# tr2_redraw.net
KiCad netlist of a schematic drawn in EAGLE
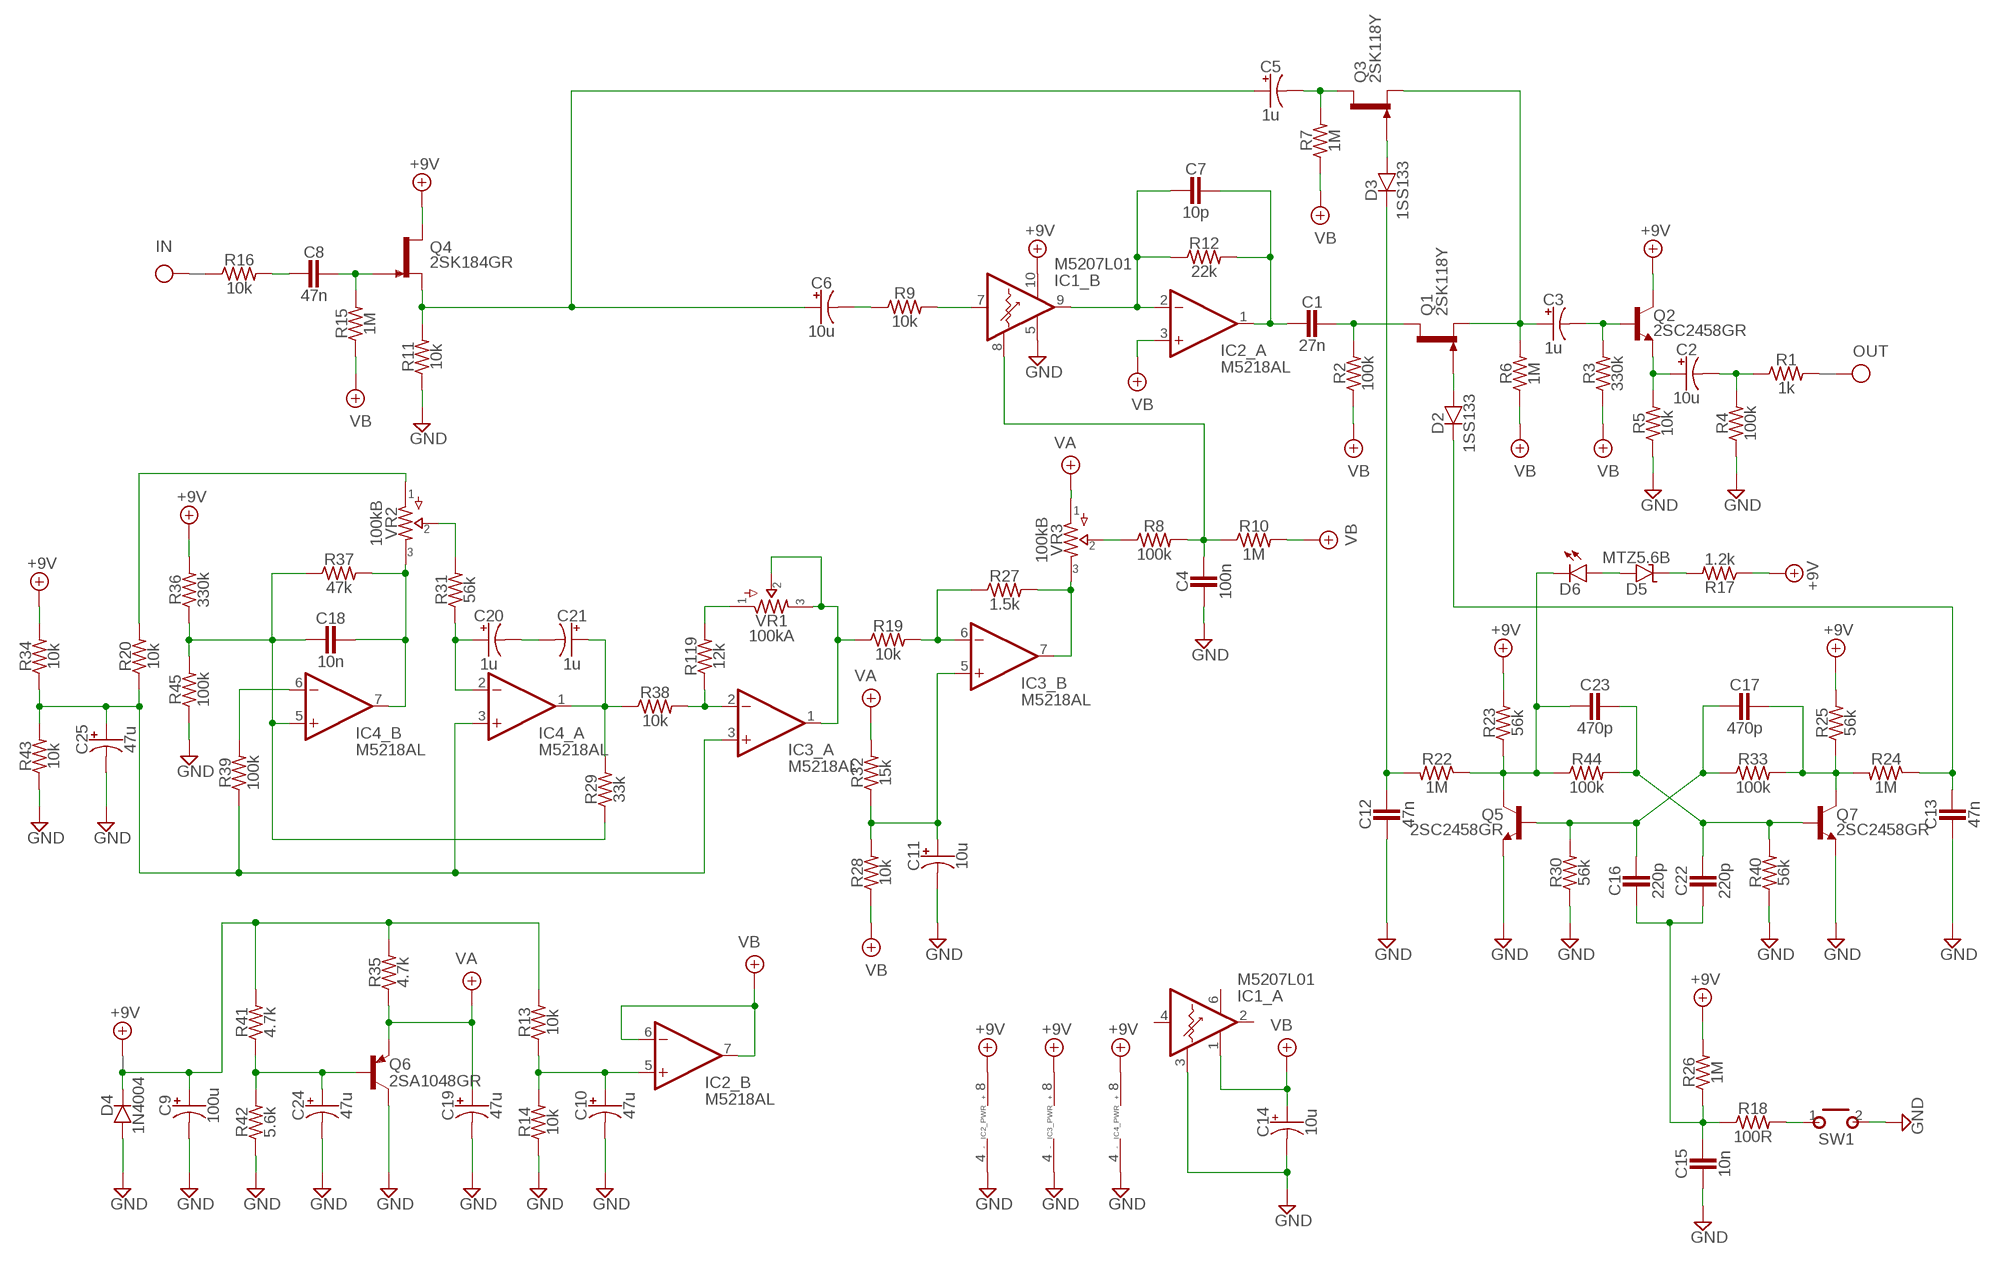
[diagram p0: schematic, sheet 1]

(export (version "E")
  (design (tool "Eeschema 10.0.6"))
  (components
    (comp (ref "C1")
      (value "27n")
      (footprint "eagle-import:BOX_SMALL")
      (libsource (lib "eagle-import") (part "CER/FILMBOX.1"))
    )
    (comp (ref "C2")
      (value "10u")
      (footprint "eagle-import:040_020")
      (libsource (lib "eagle-import") (part "0400"))
    )
    (comp (ref "C3")
      (value "1u")
      (footprint "eagle-import:040_020")
      (libsource (lib "eagle-import") (part "0400"))
    )
    (comp (ref "C4")
      (value "100n")
      (footprint "eagle-import:BOX_SMALL")
      (libsource (lib "eagle-import") (part "CER/FILMBOX.1"))
    )
    (comp (ref "C5")
      (value "1u")
      (footprint "eagle-import:040_020")
      (libsource (lib "eagle-import") (part "0400"))
    )
    (comp (ref "C6")
      (value "10u")
      (footprint "eagle-import:040_020")
      (libsource (lib "eagle-import") (part "0400"))
    )
    (comp (ref "C7")
      (value "10p")
      (footprint "eagle-import:BOX_SMALL")
      (libsource (lib "eagle-import") (part "CER/FILMBOX.1"))
    )
    (comp (ref "C8")
      (value "47n")
      (footprint "eagle-import:BOX_SMALL")
      (libsource (lib "eagle-import") (part "CER/FILMBOX.1"))
    )
    (comp (ref "C9")
      (value "100u")
      (footprint "eagle-import:040_020")
      (libsource (lib "eagle-import") (part "0400"))
    )
    (comp (ref "C10")
      (value "47u")
      (footprint "eagle-import:040_020")
      (libsource (lib "eagle-import") (part "0400"))
    )
    (comp (ref "C11")
      (value "10u")
      (footprint "eagle-import:040_020")
      (libsource (lib "eagle-import") (part "0400"))
    )
    (comp (ref "C12")
      (value "47n")
      (footprint "eagle-import:BOX_SMALL")
      (libsource (lib "eagle-import") (part "CER/FILMBOX.1"))
    )
    (comp (ref "C13")
      (value "47n")
      (footprint "eagle-import:BOX_SMALL")
      (libsource (lib "eagle-import") (part "CER/FILMBOX.1"))
    )
    (comp (ref "C14")
      (value "10u")
      (footprint "eagle-import:040_020")
      (libsource (lib "eagle-import") (part "0400"))
    )
    (comp (ref "C15")
      (value "10n")
      (footprint "eagle-import:BOX_SMALL")
      (libsource (lib "eagle-import") (part "CER/FILMBOX.1"))
    )
    (comp (ref "C16")
      (value "220p")
      (footprint "eagle-import:BOX_SMALL")
      (libsource (lib "eagle-import") (part "CER/FILMBOX.1"))
    )
    (comp (ref "C17")
      (value "470p")
      (footprint "eagle-import:BOX_SMALL")
      (libsource (lib "eagle-import") (part "CER/FILMBOX.1"))
    )
    (comp (ref "C18")
      (value "10n")
      (footprint "eagle-import:BOX_SMALL")
      (libsource (lib "eagle-import") (part "CER/FILMBOX.1"))
    )
    (comp (ref "C19")
      (value "47u")
      (footprint "eagle-import:040_020")
      (libsource (lib "eagle-import") (part "0400"))
    )
    (comp (ref "C20")
      (value "1u")
      (footprint "eagle-import:040_020")
      (libsource (lib "eagle-import") (part "0400"))
    )
    (comp (ref "C21")
      (value "1u")
      (footprint "eagle-import:040_020")
      (libsource (lib "eagle-import") (part "0400"))
    )
    (comp (ref "C22")
      (value "220p")
      (footprint "eagle-import:BOX_SMALL")
      (libsource (lib "eagle-import") (part "CER/FILMBOX.1"))
    )
    (comp (ref "C23")
      (value "470p")
      (footprint "eagle-import:BOX_SMALL")
      (libsource (lib "eagle-import") (part "CER/FILMBOX.1"))
    )
    (comp (ref "C24")
      (value "47u")
      (footprint "eagle-import:040_020")
      (libsource (lib "eagle-import") (part "0400"))
    )
    (comp (ref "C25")
      (value "47u")
      (footprint "eagle-import:040_020")
      (libsource (lib "eagle-import") (part "0400"))
    )
    (comp (ref "D2")
      (value "1SS133")
      (footprint "eagle-import:DO35-2")
      (libsource (lib "eagle-import") (part "DO35.2"))
    )
    (comp (ref "D3")
      (value "1SS133")
      (footprint "eagle-import:DO35-2")
      (libsource (lib "eagle-import") (part "DO35.2"))
    )
    (comp (ref "D4")
      (value "1N4004")
      (footprint "eagle-import:DO35-2")
      (libsource (lib "eagle-import") (part "DO35.2"))
    )
    (comp (ref "D5")
      (value "MTZ5.6B")
      (footprint "eagle-import:DO41-2")
      (libsource (lib "eagle-import") (part "ZENER.2"))
    )
    (comp (ref "D6")
      (value "LN-28RP")
      (footprint "eagle-import:3MM_D")
      (libsource (lib "eagle-import") (part "LED"))
    )
    (comp (ref "IC1")
      (value "M5207L01")
      (footprint "eagle-import:SIL10")
      (libsource (lib "eagle-import") (part "M5207L01"))
    )
    (comp (ref "IC2")
      (value "M5218AL")
      (footprint "eagle-import:DIL0")
      (libsource (lib "eagle-import") (part "DUALTH"))
    )
    (comp (ref "IC3")
      (value "M5218AL")
      (footprint "eagle-import:DIL0")
      (libsource (lib "eagle-import") (part "DUALTH"))
    )
    (comp (ref "IC4")
      (value "M5218AL")
      (footprint "eagle-import:DIL0")
      (libsource (lib "eagle-import") (part "DUALTH"))
    )
    (comp (ref "Q1")
      (value "2SK118Y")
      (footprint "eagle-import:TO92-")
      (libsource (lib "eagle-import") (part "2N3819TO-92S"))
    )
    (comp (ref "Q2")
      (value "2SC2458GR")
      (footprint "eagle-import:TO92-")
      (libsource (lib "eagle-import") (part "2SC828A"))
    )
    (comp (ref "Q3")
      (value "2SK118Y")
      (footprint "eagle-import:TO92-")
      (libsource (lib "eagle-import") (part "2N3819TO-92S"))
    )
    (comp (ref "Q4")
      (value "2SK184GR")
      (footprint "eagle-import:TO92-")
      (libsource (lib "eagle-import") (part "2N3819TO-92S"))
    )
    (comp (ref "Q5")
      (value "2SC2458GR")
      (footprint "eagle-import:TO92-")
      (libsource (lib "eagle-import") (part "2SC828A"))
    )
    (comp (ref "Q6")
      (value "2SA1048GR")
      (footprint "eagle-import:TO92-")
      (libsource (lib "eagle-import") (part "2N3906-"))
    )
    (comp (ref "Q7")
      (value "2SC2458GR")
      (footprint "eagle-import:TO92-")
      (libsource (lib "eagle-import") (part "2SC828A"))
    )
    (comp (ref "R1")
      (value "1k")
      (footprint "eagle-import:R0207_3")
      (libsource (lib "eagle-import") (part "R_.3B"))
    )
    (comp (ref "R2")
      (value "100k")
      (footprint "eagle-import:R0207_3")
      (libsource (lib "eagle-import") (part "R_.3B"))
    )
    (comp (ref "R3")
      (value "330k")
      (footprint "eagle-import:R0207_3")
      (libsource (lib "eagle-import") (part "R_.3B"))
    )
    (comp (ref "R4")
      (value "100k")
      (footprint "eagle-import:R0207_3")
      (libsource (lib "eagle-import") (part "R_.3B"))
    )
    (comp (ref "R5")
      (value "10k")
      (footprint "eagle-import:R0207_3")
      (libsource (lib "eagle-import") (part "R_.3B"))
    )
    (comp (ref "R6")
      (value "1M")
      (footprint "eagle-import:R0207_3")
      (libsource (lib "eagle-import") (part "R_.3B"))
    )
    (comp (ref "R7")
      (value "1M")
      (footprint "eagle-import:R0207_3")
      (libsource (lib "eagle-import") (part "R_.3B"))
    )
    (comp (ref "R8")
      (value "100k")
      (footprint "eagle-import:R0207_3")
      (libsource (lib "eagle-import") (part "R_.3B"))
    )
    (comp (ref "R9")
      (value "10k")
      (footprint "eagle-import:R0207_3")
      (libsource (lib "eagle-import") (part "R_.3B"))
    )
    (comp (ref "R10")
      (value "1M")
      (footprint "eagle-import:R0207_3")
      (libsource (lib "eagle-import") (part "R_.3B"))
    )
    (comp (ref "R11")
      (value "10k")
      (footprint "eagle-import:R0207_3")
      (libsource (lib "eagle-import") (part "R_.3B"))
    )
    (comp (ref "R12")
      (value "22k")
      (footprint "eagle-import:R0207_3")
      (libsource (lib "eagle-import") (part "R_.3B"))
    )
    (comp (ref "R13")
      (value "10k")
      (footprint "eagle-import:R0207_3")
      (libsource (lib "eagle-import") (part "R_.3B"))
    )
    (comp (ref "R14")
      (value "10k")
      (footprint "eagle-import:R0207_3")
      (libsource (lib "eagle-import") (part "R_.3B"))
    )
    (comp (ref "R15")
      (value "1M")
      (footprint "eagle-import:R0207_3")
      (libsource (lib "eagle-import") (part "R_.3B"))
    )
    (comp (ref "R16")
      (value "10k")
      (footprint "eagle-import:R0207_3")
      (libsource (lib "eagle-import") (part "R_.3B"))
    )
    (comp (ref "R17")
      (value "1.2k")
      (footprint "eagle-import:R0207_3")
      (libsource (lib "eagle-import") (part "R_.3B"))
    )
    (comp (ref "R18")
      (value "100R")
      (footprint "eagle-import:R0207_3")
      (libsource (lib "eagle-import") (part "R_.3B"))
    )
    (comp (ref "R19")
      (value "10k")
      (footprint "eagle-import:R0207_3")
      (libsource (lib "eagle-import") (part "R_.3B"))
    )
    (comp (ref "R20")
      (value "10k")
      (footprint "eagle-import:R0207_3")
      (libsource (lib "eagle-import") (part "R_.3B"))
    )
    (comp (ref "R22")
      (value "1M")
      (footprint "eagle-import:R0207_3")
      (libsource (lib "eagle-import") (part "R_.3B"))
    )
    (comp (ref "R23")
      (value "56k")
      (footprint "eagle-import:R0207_3")
      (libsource (lib "eagle-import") (part "R_.3B"))
    )
    (comp (ref "R24")
      (value "1M")
      (footprint "eagle-import:R0207_3")
      (libsource (lib "eagle-import") (part "R_.3B"))
    )
    (comp (ref "R25")
      (value "56k")
      (footprint "eagle-import:R0207_3")
      (libsource (lib "eagle-import") (part "R_.3B"))
    )
    (comp (ref "R26")
      (value "1M")
      (footprint "eagle-import:R0207_3")
      (libsource (lib "eagle-import") (part "R_.3B"))
    )
    (comp (ref "R27")
      (value "1.5k")
      (footprint "eagle-import:R0207_3")
      (libsource (lib "eagle-import") (part "R_.3B"))
    )
    (comp (ref "R28")
      (value "10k")
      (footprint "eagle-import:R0207_3")
      (libsource (lib "eagle-import") (part "R_.3B"))
    )
    (comp (ref "R29")
      (value "33k")
      (footprint "eagle-import:R0207_3")
      (libsource (lib "eagle-import") (part "R_.3B"))
    )
    (comp (ref "R30")
      (value "56k")
      (footprint "eagle-import:R0207_3")
      (libsource (lib "eagle-import") (part "R_.3B"))
    )
    (comp (ref "R31")
      (value "56k")
      (footprint "eagle-import:R0207_3")
      (libsource (lib "eagle-import") (part "R_.3B"))
    )
    (comp (ref "R32")
      (value "15k")
      (footprint "eagle-import:R0207_3")
      (libsource (lib "eagle-import") (part "R_.3B"))
    )
    (comp (ref "R33")
      (value "100k")
      (footprint "eagle-import:R0207_3")
      (libsource (lib "eagle-import") (part "R_.3B"))
    )
    (comp (ref "R34")
      (value "10k")
      (footprint "eagle-import:R0207_3")
      (libsource (lib "eagle-import") (part "R_.3B"))
    )
    (comp (ref "R35")
      (value "4.7k")
      (footprint "eagle-import:R0207_3")
      (libsource (lib "eagle-import") (part "R_.3B"))
    )
    (comp (ref "R36")
      (value "330k")
      (footprint "eagle-import:R0207_3")
      (libsource (lib "eagle-import") (part "R_.3B"))
    )
    (comp (ref "R37")
      (value "47k")
      (footprint "eagle-import:R0207_3")
      (libsource (lib "eagle-import") (part "R_.3B"))
    )
    (comp (ref "R38")
      (value "10k")
      (footprint "eagle-import:R0207_3")
      (libsource (lib "eagle-import") (part "R_.3B"))
    )
    (comp (ref "R39")
      (value "100k")
      (footprint "eagle-import:R0207_3")
      (libsource (lib "eagle-import") (part "R_.3B"))
    )
    (comp (ref "R40")
      (value "56k")
      (footprint "eagle-import:R0207_3")
      (libsource (lib "eagle-import") (part "R_.3B"))
    )
    (comp (ref "R41")
      (value "4.7k")
      (footprint "eagle-import:R0207_3")
      (libsource (lib "eagle-import") (part "R_.3B"))
    )
    (comp (ref "R42")
      (value "5.6k")
      (footprint "eagle-import:R0207_3")
      (libsource (lib "eagle-import") (part "R_.3B"))
    )
    (comp (ref "R43")
      (value "10k")
      (footprint "eagle-import:R0207_3")
      (libsource (lib "eagle-import") (part "R_.3B"))
    )
    (comp (ref "R44")
      (value "100k")
      (footprint "eagle-import:R0207_3")
      (libsource (lib "eagle-import") (part "R_.3B"))
    )
    (comp (ref "R45")
      (value "100k")
      (footprint "eagle-import:R0207_3")
      (libsource (lib "eagle-import") (part "R_.3B"))
    )
    (comp (ref "R119")
      (value "12k")
      (footprint "eagle-import:R0207_3")
      (libsource (lib "eagle-import") (part "R_.3B"))
    )
    (comp (ref "SW1")
      (value "MOMENTARY")
      (footprint "eagle-import:SPST")
      (libsource (lib "eagle-import") (part "MOMENTARY"))
    )
    (comp (ref "VR1")
      (value "100kA")
      (footprint "eagle-import:16MM")
      (libsource (lib "eagle-import") (part "POTS16MM"))
    )
    (comp (ref "VR2")
      (value "100kB")
      (footprint "eagle-import:16MM")
      (libsource (lib "eagle-import") (part "POTS16MM"))
    )
    (comp (ref "VR3")
      (value "100kB")
      (footprint "eagle-import:16MM")
      (libsource (lib "eagle-import") (part "POTS16MM"))
    )
  )
  (nets
    (net (code "1") (name "+9V") (class "Default")
      (node (ref "IC1") (pin "10") (pinfunction "+PWR_10") (pintype "power_in"))
      (node (ref "IC2") (pin "8") (pinfunction "V+_8") (pintype "power_in"))
      (node (ref "IC3") (pin "8") (pinfunction "V+_8") (pintype "power_in"))
      (node (ref "IC4") (pin "8") (pinfunction "V+_8") (pintype "power_in"))
      (node (ref "Q2") (pin "2") (pinfunction "C_2") (pintype "passive"))
      (node (ref "Q4") (pin "3") (pinfunction "D_3") (pintype "passive"))
      (node (ref "R17") (pin "1") (pinfunction "1_1") (pintype "passive"))
      (node (ref "R23") (pin "2") (pinfunction "2_2") (pintype "passive"))
      (node (ref "R25") (pin "2") (pinfunction "2_2") (pintype "passive"))
      (node (ref "R26") (pin "2") (pinfunction "2_2") (pintype "passive"))
      (node (ref "R34") (pin "2") (pinfunction "2_2") (pintype "passive"))
      (node (ref "R36") (pin "2") (pinfunction "2_2") (pintype "passive"))
    )
    (net (code "2") (name "/+PWR") (class "Default")
      (node (ref "IC1") (pin "6") (pinfunction "+PWR_6") (pintype "power_in"))
    )
    (net (code "3") (name "GND") (class "Default")
      (node (ref "C10") (pin "-") (pinfunction "-_-") (pintype "passive"))
      (node (ref "C11") (pin "-") (pinfunction "-_-") (pintype "passive"))
      (node (ref "C12") (pin "2") (pinfunction "2_2") (pintype "passive"))
      (node (ref "C13") (pin "2") (pinfunction "2_2") (pintype "passive"))
      (node (ref "C14") (pin "-") (pinfunction "-_-") (pintype "passive"))
      (node (ref "C15") (pin "2") (pinfunction "2_2") (pintype "passive"))
      (node (ref "C19") (pin "-") (pinfunction "-_-") (pintype "passive"))
      (node (ref "C24") (pin "-") (pinfunction "-_-") (pintype "passive"))
      (node (ref "C25") (pin "-") (pinfunction "-_-") (pintype "passive"))
      (node (ref "C4") (pin "2") (pinfunction "2_2") (pintype "passive"))
      (node (ref "C9") (pin "-") (pinfunction "-_-") (pintype "passive"))
      (node (ref "D4") (pin "A") (pinfunction "A_A") (pintype "passive"))
      (node (ref "IC1") (pin "3") (pinfunction "VC_3") (pintype "bidirectional"))
      (node (ref "IC1") (pin "5") (pinfunction "-PWR_5") (pintype "power_in"))
      (node (ref "IC2") (pin "4") (pinfunction "V-_4") (pintype "power_in"))
      (node (ref "IC3") (pin "4") (pinfunction "V-_4") (pintype "power_in"))
      (node (ref "IC4") (pin "4") (pinfunction "V-_4") (pintype "power_in"))
      (node (ref "Q5") (pin "3") (pinfunction "E_3") (pintype "passive"))
      (node (ref "Q6") (pin "1") (pinfunction "C_1") (pintype "passive"))
      (node (ref "Q7") (pin "3") (pinfunction "E_3") (pintype "passive"))
      (node (ref "R11") (pin "1") (pinfunction "1_1") (pintype "passive"))
      (node (ref "R14") (pin "1") (pinfunction "1_1") (pintype "passive"))
      (node (ref "R30") (pin "1") (pinfunction "1_1") (pintype "passive"))
      (node (ref "R4") (pin "1") (pinfunction "1_1") (pintype "passive"))
      (node (ref "R40") (pin "1") (pinfunction "1_1") (pintype "passive"))
      (node (ref "R42") (pin "1") (pinfunction "1_1") (pintype "passive"))
      (node (ref "R43") (pin "1") (pinfunction "1_1") (pintype "passive"))
      (node (ref "R45") (pin "1") (pinfunction "1_1") (pintype "passive"))
      (node (ref "R5") (pin "1") (pinfunction "1_1") (pintype "passive"))
      (node (ref "SW1") (pin "2") (pinfunction "S_2") (pintype "passive"))
    )
    (net (code "5") (name "Net-(C2-Pad-)") (class "Default")
      (node (ref "C2") (pin "-") (pinfunction "-_-") (pintype "passive"))
      (node (ref "R1") (pin "1") (pinfunction "1_1") (pintype "passive"))
      (node (ref "R4") (pin "2") (pinfunction "2_2") (pintype "passive"))
    )
    (net (code "6") (name "Net-(C6-Pad-)") (class "Default")
      (node (ref "C6") (pin "-") (pinfunction "-_-") (pintype "passive"))
      (node (ref "R9") (pin "1") (pinfunction "1_1") (pintype "passive"))
    )
    (net (code "7") (name "Net-(C8-Pad2)") (class "Default")
      (node (ref "C8") (pin "2") (pinfunction "2_2") (pintype "passive"))
      (node (ref "R16") (pin "2") (pinfunction "2_2") (pintype "passive"))
    )
    (net (code "8") (name "Net-(C9-Pad+)") (class "Default")
      (node (ref "C9") (pin "+") (pinfunction "+_+") (pintype "passive"))
      (node (ref "D4") (pin "C") (pinfunction "C_C") (pintype "passive"))
      (node (ref "R13") (pin "2") (pinfunction "2_2") (pintype "passive"))
      (node (ref "R35") (pin "2") (pinfunction "2_2") (pintype "passive"))
      (node (ref "R41") (pin "2") (pinfunction "2_2") (pintype "passive"))
    )
    (net (code "9") (name "Net-(C12-Pad1)") (class "Default")
      (node (ref "C12") (pin "1") (pinfunction "1_1") (pintype "passive"))
      (node (ref "D3") (pin "C") (pinfunction "C_C") (pintype "passive"))
      (node (ref "R22") (pin "2") (pinfunction "2_2") (pintype "passive"))
    )
    (net (code "10") (name "Net-(C13-Pad1)") (class "Default")
      (node (ref "C13") (pin "1") (pinfunction "1_1") (pintype "passive"))
      (node (ref "D2") (pin "C") (pinfunction "C_C") (pintype "passive"))
      (node (ref "R24") (pin "1") (pinfunction "1_1") (pintype "passive"))
    )
    (net (code "11") (name "Net-(C15-Pad1)") (class "Default")
      (node (ref "C15") (pin "1") (pinfunction "1_1") (pintype "passive"))
      (node (ref "C16") (pin "2") (pinfunction "2_2") (pintype "passive"))
      (node (ref "C22") (pin "2") (pinfunction "2_2") (pintype "passive"))
      (node (ref "R18") (pin "1") (pinfunction "1_1") (pintype "passive"))
      (node (ref "R26") (pin "1") (pinfunction "1_1") (pintype "passive"))
    )
    (net (code "12") (name "Net-(C20-Pad-)") (class "Default")
      (node (ref "C20") (pin "-") (pinfunction "-_-") (pintype "passive"))
      (node (ref "C21") (pin "-") (pinfunction "-_-") (pintype "passive"))
    )
    (net (code "13") (name "Net-(D5-PadC)") (class "Default")
      (node (ref "D5") (pin "C") (pinfunction "C_C") (pintype "passive"))
      (node (ref "R17") (pin "2") (pinfunction "2_2") (pintype "passive"))
    )
    (net (code "14") (name "Net-(D6-A)") (class "Default")
      (node (ref "D5") (pin "A") (pinfunction "A_A") (pintype "passive"))
      (node (ref "D6") (pin "ANODE") (pinfunction "A_ANODE") (pintype "passive"))
    )
    (net (code "15") (name "Net-(D6-C)") (class "Default")
      (node (ref "C23") (pin "2") (pinfunction "2_2") (pintype "passive"))
      (node (ref "D6") (pin "P$1") (pinfunction "C_P$1") (pintype "passive"))
      (node (ref "Q5") (pin "2") (pinfunction "C_2") (pintype "passive"))
      (node (ref "R22") (pin "1") (pinfunction "1_1") (pintype "passive"))
      (node (ref "R23") (pin "1") (pinfunction "1_1") (pintype "passive"))
      (node (ref "R44") (pin "1") (pinfunction "1_1") (pintype "passive"))
    )
    (net (code "16") (name "Net-(IC1B-IN)") (class "Default")
      (node (ref "IC1") (pin "7") (pinfunction "IN_7") (pintype "input"))
      (node (ref "R9") (pin "2") (pinfunction "2_2") (pintype "passive"))
    )
    (net (code "17") (name "Net-(IC1B-OUT)") (class "Default")
      (node (ref "C7") (pin "2") (pinfunction "2_2") (pintype "passive"))
      (node (ref "IC1") (pin "9") (pinfunction "OUT_9") (pintype "output"))
      (node (ref "IC2") (pin "2") (pinfunction "-IN_2") (pintype "input"))
      (node (ref "R12") (pin "1") (pinfunction "1_1") (pintype "passive"))
    )
    (net (code "18") (name "Net-(IC1B-VC)") (class "Default")
      (node (ref "C4") (pin "1") (pinfunction "1_1") (pintype "passive"))
      (node (ref "IC1") (pin "8") (pinfunction "VC_8") (pintype "bidirectional"))
      (node (ref "R10") (pin "1") (pinfunction "1_1") (pintype "passive"))
      (node (ref "R8") (pin "2") (pinfunction "2_2") (pintype "passive"))
    )
    (net (code "19") (name "Net-(IC2A-OUT)") (class "Default")
      (node (ref "C1") (pin "2") (pinfunction "2_2") (pintype "passive"))
      (node (ref "C7") (pin "1") (pinfunction "1_1") (pintype "passive"))
      (node (ref "IC2") (pin "1") (pinfunction "OUT_1") (pintype "output"))
      (node (ref "R12") (pin "2") (pinfunction "2_2") (pintype "passive"))
    )
    (net (code "20") (name "Net-(IC2B-+IN)") (class "Default")
      (node (ref "C10") (pin "+") (pinfunction "+_+") (pintype "passive"))
      (node (ref "IC2") (pin "5") (pinfunction "+IN_5") (pintype "input"))
      (node (ref "R13") (pin "1") (pinfunction "1_1") (pintype "passive"))
      (node (ref "R14") (pin "2") (pinfunction "2_2") (pintype "passive"))
    )
    (net (code "21") (name "Net-(IC3A-+IN)") (class "Default")
      (node (ref "C25") (pin "+") (pinfunction "+_+") (pintype "passive"))
      (node (ref "IC3") (pin "3") (pinfunction "+IN_3") (pintype "input"))
      (node (ref "IC4") (pin "3") (pinfunction "+IN_3") (pintype "input"))
      (node (ref "R20") (pin "1") (pinfunction "1_1") (pintype "passive"))
      (node (ref "R34") (pin "1") (pinfunction "1_1") (pintype "passive"))
      (node (ref "R39") (pin "1") (pinfunction "1_1") (pintype "passive"))
      (node (ref "R43") (pin "2") (pinfunction "2_2") (pintype "passive"))
    )
    (net (code "22") (name "Net-(IC3A--IN)") (class "Default")
      (node (ref "IC3") (pin "2") (pinfunction "-IN_2") (pintype "input"))
      (node (ref "R119") (pin "1") (pinfunction "1_1") (pintype "passive"))
      (node (ref "R38") (pin "2") (pinfunction "2_2") (pintype "passive"))
    )
    (net (code "23") (name "Net-(IC3A-OUT)") (class "Default")
      (node (ref "IC3") (pin "1") (pinfunction "OUT_1") (pintype "output"))
      (node (ref "R19") (pin "1") (pinfunction "1_1") (pintype "passive"))
      (node (ref "VR1") (pin "2") (pinfunction "2_2") (pintype "passive"))
      (node (ref "VR1") (pin "3") (pinfunction "3_3") (pintype "passive"))
    )
    (net (code "24") (name "Net-(IC3B-+IN)") (class "Default")
      (node (ref "C11") (pin "+") (pinfunction "+_+") (pintype "passive"))
      (node (ref "IC3") (pin "5") (pinfunction "+IN_5") (pintype "input"))
      (node (ref "R28") (pin "2") (pinfunction "2_2") (pintype "passive"))
      (node (ref "R32") (pin "1") (pinfunction "1_1") (pintype "passive"))
    )
    (net (code "25") (name "Net-(IC3B--IN)") (class "Default")
      (node (ref "IC3") (pin "6") (pinfunction "-IN_6") (pintype "input"))
      (node (ref "R19") (pin "2") (pinfunction "2_2") (pintype "passive"))
      (node (ref "R27") (pin "1") (pinfunction "1_1") (pintype "passive"))
    )
    (net (code "26") (name "Net-(IC3B-OUT)") (class "Default")
      (node (ref "IC3") (pin "7") (pinfunction "OUT_7") (pintype "output"))
      (node (ref "R27") (pin "2") (pinfunction "2_2") (pintype "passive"))
      (node (ref "VR3") (pin "3") (pinfunction "3_3") (pintype "passive"))
    )
    (net (code "27") (name "Net-(IC4A--IN)") (class "Default")
      (node (ref "C20") (pin "+") (pinfunction "+_+") (pintype "passive"))
      (node (ref "IC4") (pin "2") (pinfunction "-IN_2") (pintype "input"))
      (node (ref "R31") (pin "1") (pinfunction "1_1") (pintype "passive"))
    )
    (net (code "28") (name "Net-(IC4A-OUT)") (class "Default")
      (node (ref "C21") (pin "+") (pinfunction "+_+") (pintype "passive"))
      (node (ref "IC4") (pin "1") (pinfunction "OUT_1") (pintype "output"))
      (node (ref "R29") (pin "2") (pinfunction "2_2") (pintype "passive"))
      (node (ref "R38") (pin "1") (pinfunction "1_1") (pintype "passive"))
    )
    (net (code "29") (name "Net-(IC4B-+IN)") (class "Default")
      (node (ref "C18") (pin "2") (pinfunction "2_2") (pintype "passive"))
      (node (ref "IC4") (pin "5") (pinfunction "+IN_5") (pintype "input"))
      (node (ref "R29") (pin "1") (pinfunction "1_1") (pintype "passive"))
      (node (ref "R36") (pin "1") (pinfunction "1_1") (pintype "passive"))
      (node (ref "R37") (pin "1") (pinfunction "1_1") (pintype "passive"))
      (node (ref "R45") (pin "2") (pinfunction "2_2") (pintype "passive"))
    )
    (net (code "30") (name "Net-(IC4B--IN)") (class "Default")
      (node (ref "IC4") (pin "6") (pinfunction "-IN_6") (pintype "input"))
      (node (ref "R39") (pin "2") (pinfunction "2_2") (pintype "passive"))
    )
    (net (code "31") (name "Net-(IC4B-OUT)") (class "Default")
      (node (ref "C18") (pin "1") (pinfunction "1_1") (pintype "passive"))
      (node (ref "IC4") (pin "7") (pinfunction "OUT_7") (pintype "output"))
      (node (ref "R37") (pin "2") (pinfunction "2_2") (pintype "passive"))
      (node (ref "VR2") (pin "3") (pinfunction "3_3") (pintype "passive"))
    )
    (net (code "32") (name "Net-(Q1-D)") (class "Default")
      (node (ref "C1") (pin "1") (pinfunction "1_1") (pintype "passive"))
      (node (ref "Q1") (pin "3") (pinfunction "D_3") (pintype "passive"))
      (node (ref "R2") (pin "2") (pinfunction "2_2") (pintype "passive"))
    )
    (net (code "33") (name "Net-(Q1-G)") (class "Default")
      (node (ref "D2") (pin "A") (pinfunction "A_A") (pintype "passive"))
      (node (ref "Q1") (pin "2") (pinfunction "G_2") (pintype "passive"))
    )
    (net (code "34") (name "Net-(Q1-S)") (class "Default")
      (node (ref "C3") (pin "+") (pinfunction "+_+") (pintype "passive"))
      (node (ref "Q1") (pin "1") (pinfunction "S_1") (pintype "passive"))
      (node (ref "Q3") (pin "1") (pinfunction "S_1") (pintype "passive"))
      (node (ref "R6") (pin "2") (pinfunction "2_2") (pintype "passive"))
    )
    (net (code "35") (name "Net-(Q2-B)") (class "Default")
      (node (ref "C3") (pin "-") (pinfunction "-_-") (pintype "passive"))
      (node (ref "Q2") (pin "1") (pinfunction "B_1") (pintype "passive"))
      (node (ref "R3") (pin "2") (pinfunction "2_2") (pintype "passive"))
    )
    (net (code "36") (name "Net-(Q2-E)") (class "Default")
      (node (ref "C2") (pin "+") (pinfunction "+_+") (pintype "passive"))
      (node (ref "Q2") (pin "3") (pinfunction "E_3") (pintype "passive"))
      (node (ref "R5") (pin "2") (pinfunction "2_2") (pintype "passive"))
    )
    (net (code "37") (name "Net-(Q3-D)") (class "Default")
      (node (ref "C5") (pin "-") (pinfunction "-_-") (pintype "passive"))
      (node (ref "Q3") (pin "3") (pinfunction "D_3") (pintype "passive"))
      (node (ref "R7") (pin "2") (pinfunction "2_2") (pintype "passive"))
    )
    (net (code "38") (name "Net-(Q3-G)") (class "Default")
      (node (ref "D3") (pin "A") (pinfunction "A_A") (pintype "passive"))
      (node (ref "Q3") (pin "2") (pinfunction "G_2") (pintype "passive"))
    )
    (net (code "39") (name "Net-(Q4-G)") (class "Default")
      (node (ref "C8") (pin "1") (pinfunction "1_1") (pintype "passive"))
      (node (ref "Q4") (pin "2") (pinfunction "G_2") (pintype "passive"))
      (node (ref "R15") (pin "2") (pinfunction "2_2") (pintype "passive"))
    )
    (net (code "40") (name "Net-(Q4-S)") (class "Default")
      (node (ref "C5") (pin "+") (pinfunction "+_+") (pintype "passive"))
      (node (ref "C6") (pin "+") (pinfunction "+_+") (pintype "passive"))
      (node (ref "Q4") (pin "1") (pinfunction "S_1") (pintype "passive"))
      (node (ref "R11") (pin "2") (pinfunction "2_2") (pintype "passive"))
    )
    (net (code "41") (name "Net-(Q5-B)") (class "Default")
      (node (ref "C16") (pin "1") (pinfunction "1_1") (pintype "passive"))
      (node (ref "C17") (pin "2") (pinfunction "2_2") (pintype "passive"))
      (node (ref "Q5") (pin "1") (pinfunction "B_1") (pintype "passive"))
      (node (ref "R30") (pin "2") (pinfunction "2_2") (pintype "passive"))
      (node (ref "R33") (pin "1") (pinfunction "1_1") (pintype "passive"))
    )
    (net (code "42") (name "Net-(Q6-B)") (class "Default")
      (node (ref "C24") (pin "+") (pinfunction "+_+") (pintype "passive"))
      (node (ref "Q6") (pin "2") (pinfunction "B_2") (pintype "passive"))
      (node (ref "R41") (pin "1") (pinfunction "1_1") (pintype "passive"))
      (node (ref "R42") (pin "2") (pinfunction "2_2") (pintype "passive"))
    )
    (net (code "43") (name "Net-(Q7-B)") (class "Default")
      (node (ref "C22") (pin "1") (pinfunction "1_1") (pintype "passive"))
      (node (ref "C23") (pin "1") (pinfunction "1_1") (pintype "passive"))
      (node (ref "Q7") (pin "1") (pinfunction "B_1") (pintype "passive"))
      (node (ref "R40") (pin "2") (pinfunction "2_2") (pintype "passive"))
      (node (ref "R44") (pin "2") (pinfunction "2_2") (pintype "passive"))
    )
    (net (code "44") (name "Net-(Q7-C)") (class "Default")
      (node (ref "C17") (pin "1") (pinfunction "1_1") (pintype "passive"))
      (node (ref "Q7") (pin "2") (pinfunction "C_2") (pintype "passive"))
      (node (ref "R24") (pin "2") (pinfunction "2_2") (pintype "passive"))
      (node (ref "R25") (pin "1") (pinfunction "1_1") (pintype "passive"))
      (node (ref "R33") (pin "2") (pinfunction "2_2") (pintype "passive"))
    )
    (net (code "45") (name "Net-(R8-Pad1)") (class "Default")
      (node (ref "R8") (pin "1") (pinfunction "1_1") (pintype "passive"))
      (node (ref "VR3") (pin "2") (pinfunction "2_2") (pintype "passive"))
    )
    (net (code "46") (name "Net-(R20-Pad2)") (class "Default")
      (node (ref "R20") (pin "2") (pinfunction "2_2") (pintype "passive"))
      (node (ref "VR2") (pin "1") (pinfunction "1_1") (pintype "passive"))
    )
    (net (code "47") (name "Net-(R31-Pad2)") (class "Default")
      (node (ref "R31") (pin "2") (pinfunction "2_2") (pintype "passive"))
      (node (ref "VR2") (pin "2") (pinfunction "2_2") (pintype "passive"))
    )
    (net (code "48") (name "Net-(R119-Pad2)") (class "Default")
      (node (ref "R119") (pin "2") (pinfunction "2_2") (pintype "passive"))
      (node (ref "VR1") (pin "1") (pinfunction "1_1") (pintype "passive"))
    )
    (net (code "49") (name "Net-(SW1-P)") (class "Default")
      (node (ref "R18") (pin "2") (pinfunction "2_2") (pintype "passive"))
      (node (ref "SW1") (pin "1") (pinfunction "P_1") (pintype "passive"))
    )
    (net (code "51") (name "VA") (class "Default")
      (node (ref "C19") (pin "+") (pinfunction "+_+") (pintype "passive"))
      (node (ref "Q6") (pin "3") (pinfunction "E_3") (pintype "passive"))
      (node (ref "R32") (pin "2") (pinfunction "2_2") (pintype "passive"))
      (node (ref "R35") (pin "1") (pinfunction "1_1") (pintype "passive"))
      (node (ref "VR3") (pin "1") (pinfunction "1_1") (pintype "passive"))
    )
    (net (code "52") (name "VB") (class "Default")
      (node (ref "C14") (pin "+") (pinfunction "+_+") (pintype "passive"))
      (node (ref "IC1") (pin "1") (pinfunction "-PWR_1") (pintype "power_in"))
      (node (ref "IC2") (pin "3") (pinfunction "+IN_3") (pintype "input"))
      (node (ref "IC2") (pin "6") (pinfunction "-IN_6") (pintype "input"))
      (node (ref "IC2") (pin "7") (pinfunction "OUT_7") (pintype "output"))
      (node (ref "R10") (pin "2") (pinfunction "2_2") (pintype "passive"))
      (node (ref "R15") (pin "1") (pinfunction "1_1") (pintype "passive"))
      (node (ref "R2") (pin "1") (pinfunction "1_1") (pintype "passive"))
      (node (ref "R28") (pin "1") (pinfunction "1_1") (pintype "passive"))
      (node (ref "R3") (pin "1") (pinfunction "1_1") (pintype "passive"))
      (node (ref "R6") (pin "1") (pinfunction "1_1") (pintype "passive"))
      (node (ref "R7") (pin "1") (pinfunction "1_1") (pintype "passive"))
    )
    (net (code "53") (name "unconnected-(IC1A-IN-Pad4)") (class "Default")
      (node (ref "IC1") (pin "4") (pinfunction "IN_4") (pintype "input"))
    )
    (net (code "54") (name "unconnected-(IC1A-OUT-Pad2)") (class "Default")
      (node (ref "IC1") (pin "2") (pinfunction "OUT_2") (pintype "output"))
    )
    (net (code "55") (name "unconnected-(R1-Pad2)") (class "Default")
      (node (ref "R1") (pin "2") (pinfunction "2_2") (pintype "passive"))
    )
    (net (code "56") (name "unconnected-(R16-Pad1)") (class "Default")
      (node (ref "R16") (pin "1") (pinfunction "1_1") (pintype "passive"))
    )
  )
)
